# Lab1_Konovalov_USB_RS485.net
KiCad netlist of a schematic drawn in Altium Designer
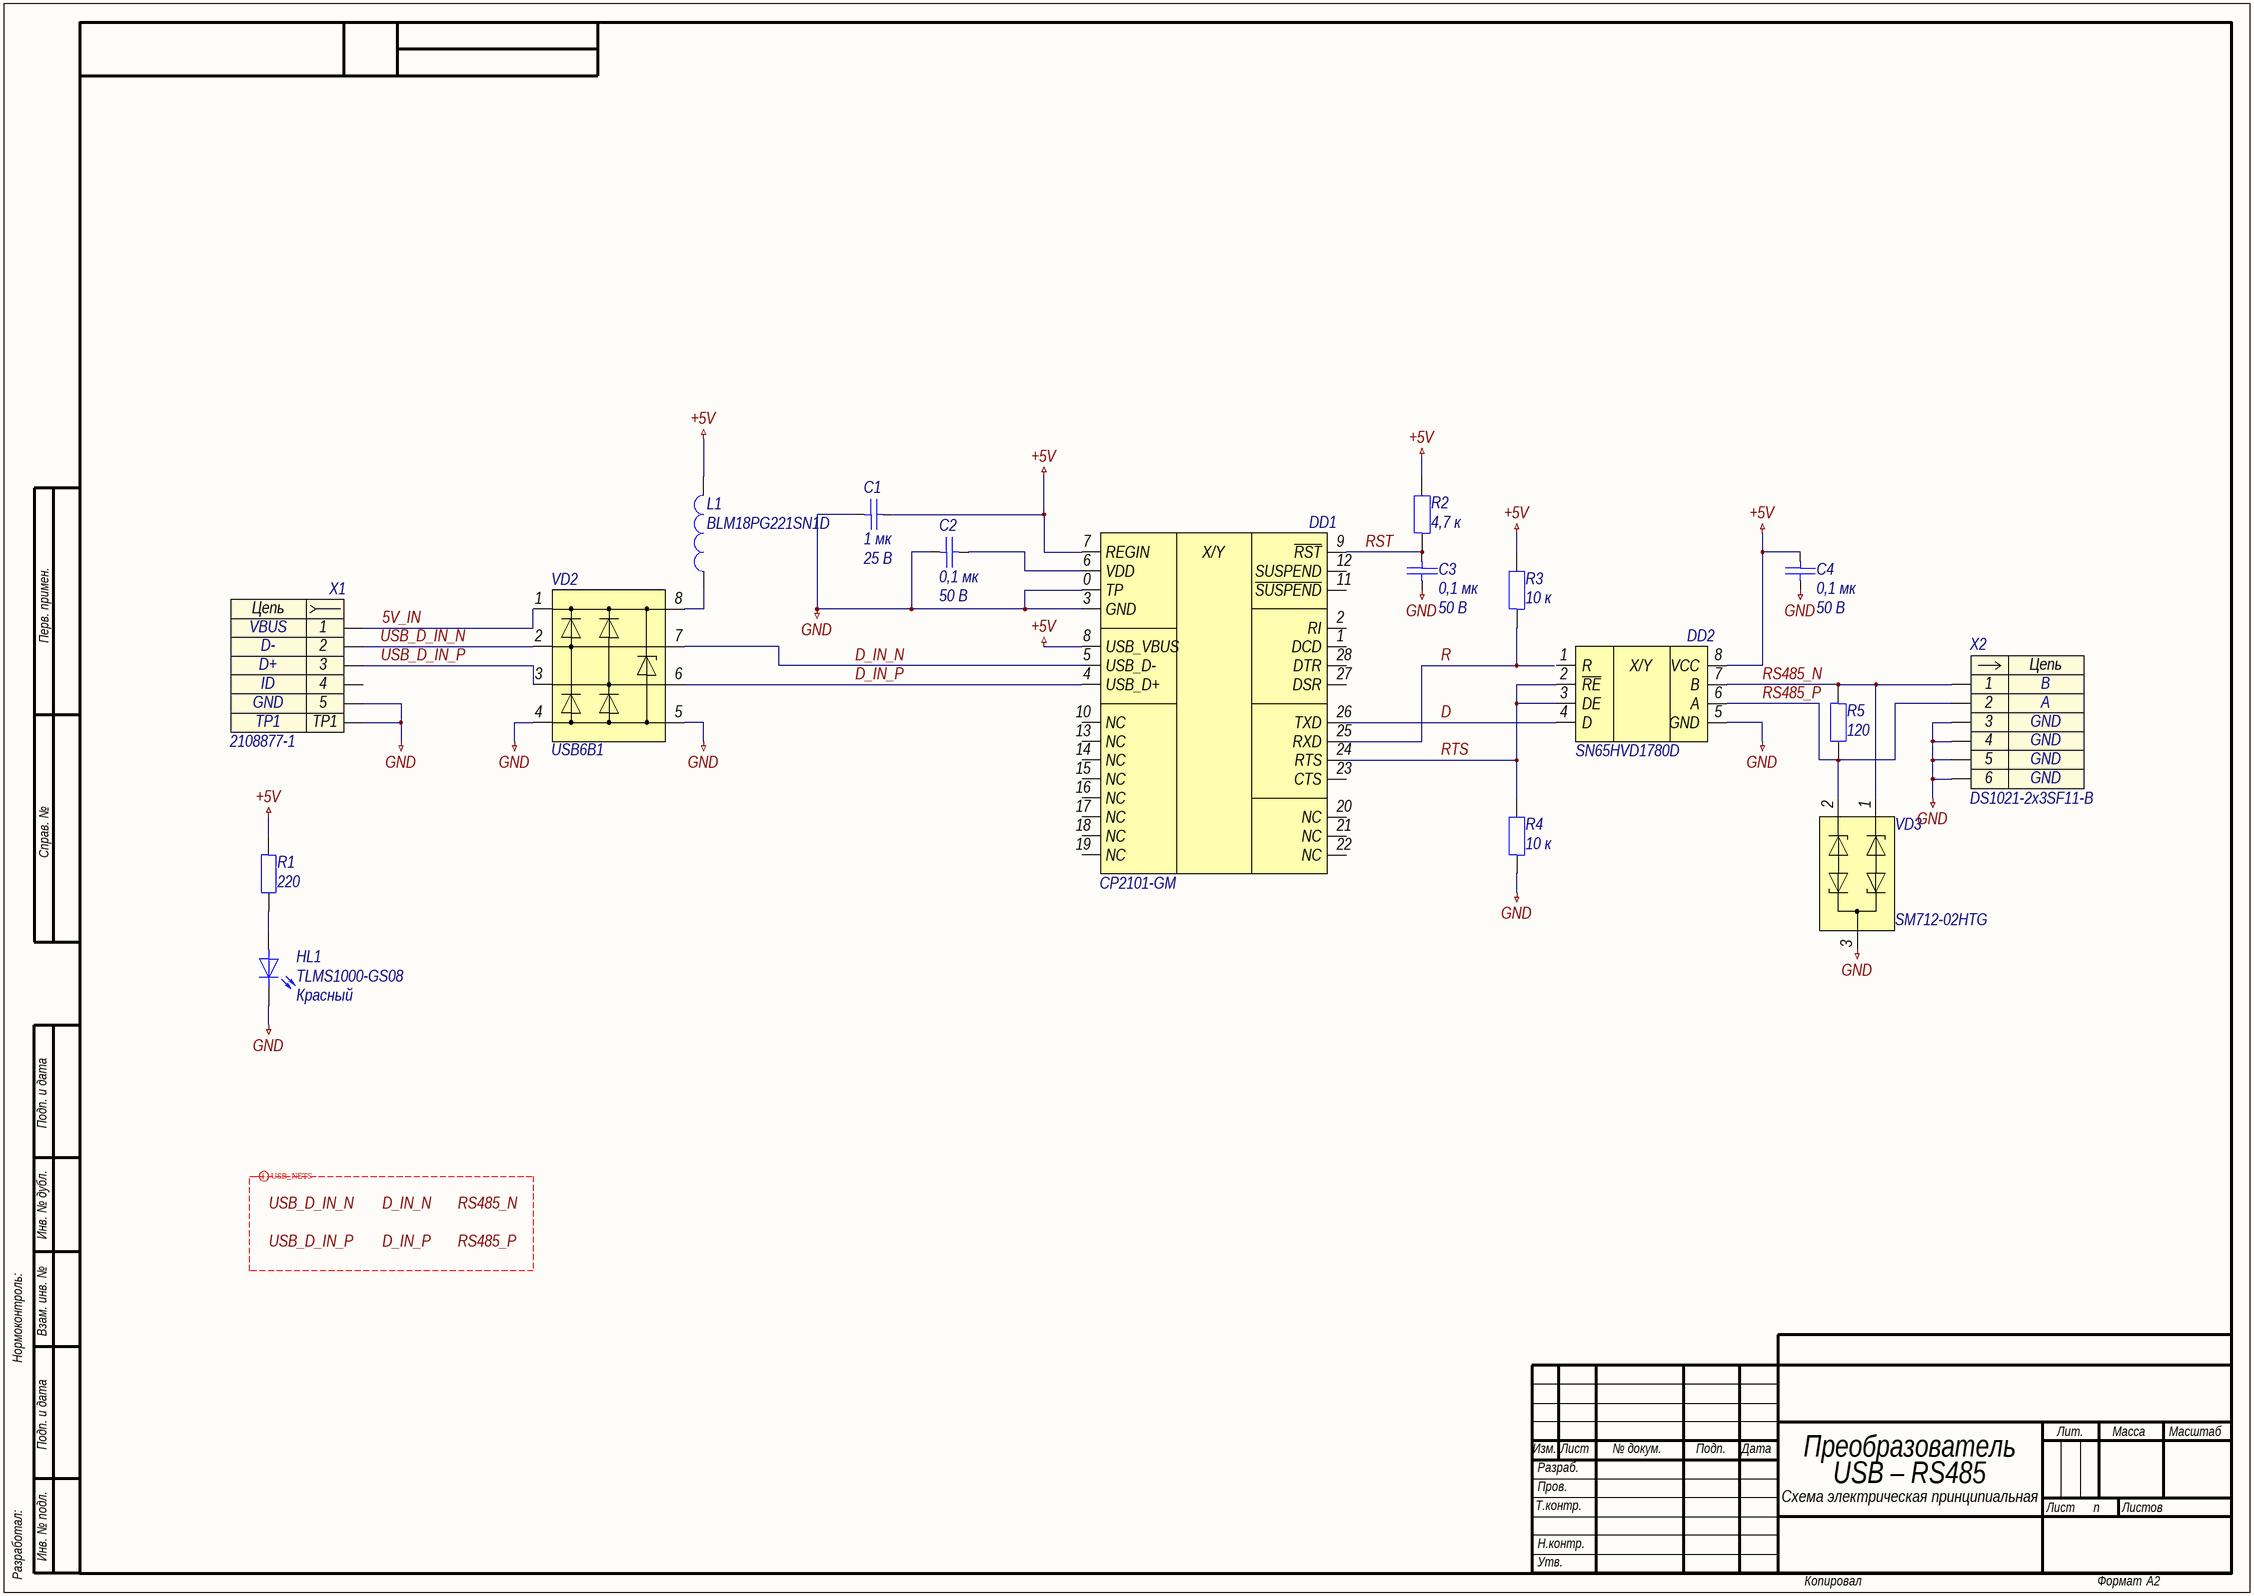
[diagram p0: Lab1_Konovalov_USB_RS485.SchDoc]

(export (version "E")
  (design (tool "Eeschema 10.0.6"))
  (components
    (comp (ref "C1")
      (value "1 мк")
      (footprint "C0603")
      (description "=Описание")
      (fields (field (name "НАПРЯЖЕНИЕ") "25 В"))
      (libsource (lib "Database_Students") (part "C-NONPOLAR"))
    )
    (comp (ref "C2")
      (value "0,1 мк")
      (footprint "C0603")
      (description "=Описание")
      (fields (field (name "НАПРЯЖЕНИЕ") "50 В"))
      (libsource (lib "Database_Students") (part "C-NONPOLAR"))
    )
    (comp (ref "C3")
      (value "0,1 мк")
      (footprint "C0603")
      (description "=Описание")
      (fields (field (name "НАПРЯЖЕНИЕ") "50 В"))
      (libsource (lib "Database_Students") (part "C-NONPOLAR"))
    )
    (comp (ref "C4")
      (value "0,1 мк")
      (footprint "C0603")
      (description "=Описание")
      (fields (field (name "НАПРЯЖЕНИЕ") "50 В"))
      (libsource (lib "Database_Students") (part "C-NONPOLAR"))
    )
    (comp (ref "DD1")
      (value "CP2101-GM")
      (footprint "QFN-28-500X500X90")
      (description "=Описание")
      (libsource (lib "Database_Students") (part "CP2101-GM"))
    )
    (comp (ref "DD2")
      (value "SN65HVD1780D")
      (footprint "SOIC-8")
      (description "=Описание")
      (libsource (lib "Database_Students") (part "SN65HVD1780D"))
    )
    (comp (ref "HL1")
      (value "TLMS1000-GS08")
      (footprint "HL0603")
      (description "=Описание")
      (fields (field (name "COLOUR") "Красный"))
      (libsource (lib "Database_Students") (part "LED-COMMON"))
    )
    (comp (ref "L1")
      (value "BLM18PG221SN1D")
      (footprint "BLM-2-0603")
      (description "=Описание")
      (libsource (lib "Database_Students") (part "FERRITE-BEAD"))
    )
    (comp (ref "R1")
      (value "220")
      (footprint "R0603")
      (description "=Описание")
      (libsource (lib "Database_Students") (part "R-COMMON"))
    )
    (comp (ref "R2")
      (value "4,7 к")
      (footprint "R0603")
      (description "=Описание")
      (libsource (lib "Database_Students") (part "R-COMMON"))
    )
    (comp (ref "R3")
      (value "10 к")
      (footprint "R0603")
      (description "=Описание")
      (libsource (lib "Database_Students") (part "R-COMMON"))
    )
    (comp (ref "R4")
      (value "10 к")
      (footprint "R0603")
      (description "=Описание")
      (libsource (lib "Database_Students") (part "R-COMMON"))
    )
    (comp (ref "R5")
      (value "120")
      (footprint "R0603")
      (description "=Описание")
      (libsource (lib "Database_Students") (part "R-COMMON"))
    )
    (comp (ref "VD2")
      (value "USB6B1")
      (footprint "SO-8")
      (description "=Описание")
      (libsource (lib "Database_Students") (part "USB6B1"))
    )
    (comp (ref "VD3")
      (value "SM712-02HTG")
      (footprint "SOT23-3")
      (description "=Описание")
      (libsource (lib "Database_Students") (part "SM712-02HTG"))
    )
    (comp (ref "X1")
      (value "2108877-1")
      (footprint "2108877-1")
      (description "=Описание")
      (libsource (lib "Database_Students") (part "HEADER-5-TP1-SCT"))
    )
    (comp (ref "X2")
      (value "DS1021-2x3SF11-B")
      (footprint "DS1021-2X3SF11-B")
      (description "=Описание")
      (libsource (lib "Database_Students") (part "HEADER-6-PLG"))
    )
  )
  (nets
    (net (code "1") (name "+5V") (class "Default")
      (node (ref "C1") (pin "1") (pinfunction "1_1") (pintype "passive"))
      (node (ref "C4") (pin "2") (pinfunction "2_2") (pintype "passive"))
      (node (ref "DD1") (pin "7") (pinfunction "REGIN_7") (pintype "passive"))
      (node (ref "DD1") (pin "8") (pinfunction "USB_VBUS_8") (pintype "passive"))
      (node (ref "DD2") (pin "8") (pinfunction "VCC_8") (pintype "passive"))
      (node (ref "L1") (pin "2") (pinfunction "2_2") (pintype "passive"))
      (node (ref "R1") (pin "1") (pinfunction "1_1") (pintype "passive"))
      (node (ref "R2") (pin "2") (pinfunction "2_2") (pintype "passive"))
      (node (ref "R3") (pin "2") (pinfunction "2_2") (pintype "passive"))
    )
    (net (code "2") (name "/5V_IN") (class "Default")
      (node (ref "VD2") (pin "1") (pinfunction "1_1") (pintype "passive"))
      (node (ref "X1") (pin "1") (pinfunction "1_1") (pintype "passive"))
    )
    (net (code "3") (name "/D") (class "Default")
      (node (ref "DD1") (pin "26") (pinfunction "TXD_26") (pintype "passive"))
      (node (ref "DD2") (pin "4") (pinfunction "D_4") (pintype "passive"))
    )
    (net (code "4") (name "/D_IN_N") (class "Default")
      (node (ref "DD1") (pin "5") (pinfunction "USB_D-_5") (pintype "passive"))
      (node (ref "VD2") (pin "7") (pinfunction "7_7") (pintype "passive"))
    )
    (net (code "5") (name "/D_IN_P") (class "Default")
      (node (ref "DD1") (pin "4") (pinfunction "USB_D+_4") (pintype "passive"))
      (node (ref "VD2") (pin "6") (pinfunction "6_6") (pintype "passive"))
    )
    (net (code "6") (name "/R") (class "Default")
      (node (ref "DD1") (pin "25") (pinfunction "RXD_25") (pintype "passive"))
      (node (ref "R3") (pin "1") (pinfunction "1_1") (pintype "passive"))
    )
    (net (code "7") (name "/RS485_N") (class "Default")
      (node (ref "DD2") (pin "7") (pinfunction "B_7") (pintype "passive"))
      (node (ref "R5") (pin "1") (pinfunction "1_1") (pintype "passive"))
      (node (ref "VD3") (pin "1") (pinfunction "1_1") (pintype "passive"))
      (node (ref "X2") (pin "1") (pinfunction "1_1") (pintype "passive"))
    )
    (net (code "8") (name "/RS485_P") (class "Default")
      (node (ref "DD2") (pin "6") (pinfunction "A_6") (pintype "passive"))
      (node (ref "R5") (pin "2") (pinfunction "2_2") (pintype "passive"))
      (node (ref "VD3") (pin "2") (pinfunction "2_2") (pintype "passive"))
      (node (ref "X2") (pin "2") (pinfunction "2_2") (pintype "passive"))
    )
    (net (code "9") (name "/RST") (class "Default")
      (node (ref "C3") (pin "2") (pinfunction "2_2") (pintype "passive"))
      (node (ref "DD1") (pin "9") (pinfunction "~{RST}_9") (pintype "passive"))
      (node (ref "R2") (pin "1") (pinfunction "1_1") (pintype "passive"))
    )
    (net (code "10") (name "/RTS") (class "Default")
      (node (ref "DD1") (pin "24") (pinfunction "RTS_24") (pintype "passive"))
      (node (ref "DD2") (pin "2") (pinfunction "~{RE}_2") (pintype "passive"))
      (node (ref "DD2") (pin "3") (pinfunction "DE_3") (pintype "passive"))
      (node (ref "R4") (pin "2") (pinfunction "2_2") (pintype "passive"))
    )
    (net (code "11") (name "/USB_D_IN_N") (class "Default")
      (node (ref "VD2") (pin "2") (pinfunction "2_2") (pintype "passive"))
      (node (ref "X1") (pin "2") (pinfunction "2_2") (pintype "passive"))
    )
    (net (code "12") (name "/USB_D_IN_P") (class "Default")
      (node (ref "VD2") (pin "3") (pinfunction "3_3") (pintype "passive"))
      (node (ref "X1") (pin "3") (pinfunction "3_3") (pintype "passive"))
    )
    (net (code "13") (name "GND") (class "Default")
      (node (ref "C1") (pin "2") (pinfunction "2_2") (pintype "passive"))
      (node (ref "C2") (pin "2") (pinfunction "2_2") (pintype "passive"))
      (node (ref "C3") (pin "1") (pinfunction "1_1") (pintype "passive"))
      (node (ref "C4") (pin "1") (pinfunction "1_1") (pintype "passive"))
      (node (ref "DD1") (pin "0") (pinfunction "TP_0") (pintype "passive"))
      (node (ref "DD1") (pin "3") (pinfunction "GND_3") (pintype "passive"))
      (node (ref "DD2") (pin "5") (pinfunction "GND_5") (pintype "passive"))
      (node (ref "HL1") (pin "1") (pinfunction "1_1") (pintype "passive"))
      (node (ref "R4") (pin "1") (pinfunction "1_1") (pintype "passive"))
      (node (ref "VD2") (pin "4") (pinfunction "4_4") (pintype "passive"))
      (node (ref "VD2") (pin "5") (pinfunction "5_5") (pintype "passive"))
      (node (ref "VD3") (pin "3") (pinfunction "3_3") (pintype "passive"))
      (node (ref "X1") (pin "5") (pinfunction "5_5") (pintype "passive"))
      (node (ref "X1") (pin "TP1") (pinfunction "TP1_TP1") (pintype "passive"))
      (node (ref "X2") (pin "3") (pinfunction "3_3") (pintype "passive"))
      (node (ref "X2") (pin "4") (pinfunction "4_4") (pintype "passive"))
      (node (ref "X2") (pin "5") (pinfunction "5_5") (pintype "passive"))
      (node (ref "X2") (pin "6") (pinfunction "6_6") (pintype "passive"))
    )
    (net (code "14") (name "Net-(DD1-VDD)") (class "Default")
      (node (ref "C2") (pin "1") (pinfunction "1_1") (pintype "passive"))
      (node (ref "DD1") (pin "6") (pinfunction "VDD_6") (pintype "passive"))
    )
    (net (code "15") (name "Net-(HL1-Pad2)") (class "Default")
      (node (ref "HL1") (pin "2") (pinfunction "2_2") (pintype "passive"))
      (node (ref "R1") (pin "2") (pinfunction "2_2") (pintype "passive"))
    )
    (net (code "16") (name "Net-(L1-Pad1)") (class "Default")
      (node (ref "L1") (pin "1") (pinfunction "1_1") (pintype "passive"))
      (node (ref "VD2") (pin "8") (pinfunction "8_8") (pintype "passive"))
    )
    (net (code "17") (name "unconnected-(DD1-CTS-Pad23)") (class "Default")
      (node (ref "DD1") (pin "23") (pinfunction "CTS_23") (pintype "passive"))
    )
    (net (code "18") (name "unconnected-(DD1-DCD-Pad1)") (class "Default")
      (node (ref "DD1") (pin "1") (pinfunction "DCD_1") (pintype "passive"))
    )
    (net (code "19") (name "unconnected-(DD1-DSR-Pad27)") (class "Default")
      (node (ref "DD1") (pin "27") (pinfunction "DSR_27") (pintype "passive"))
    )
    (net (code "20") (name "unconnected-(DD1-DTR-Pad28)") (class "Default")
      (node (ref "DD1") (pin "28") (pinfunction "DTR_28") (pintype "passive"))
    )
    (net (code "21") (name "unconnected-(DD1-NC-Pad10)") (class "Default")
      (node (ref "DD1") (pin "10") (pinfunction "NC_10") (pintype "passive"))
    )
    (net (code "22") (name "unconnected-(DD1-NC-Pad13)") (class "Default")
      (node (ref "DD1") (pin "13") (pinfunction "NC_13") (pintype "passive"))
    )
    (net (code "23") (name "unconnected-(DD1-NC-Pad14)") (class "Default")
      (node (ref "DD1") (pin "14") (pinfunction "NC_14") (pintype "passive"))
    )
    (net (code "24") (name "unconnected-(DD1-NC-Pad15)") (class "Default")
      (node (ref "DD1") (pin "15") (pinfunction "NC_15") (pintype "passive"))
    )
    (net (code "25") (name "unconnected-(DD1-NC-Pad16)") (class "Default")
      (node (ref "DD1") (pin "16") (pinfunction "NC_16") (pintype "passive"))
    )
    (net (code "26") (name "unconnected-(DD1-NC-Pad17)") (class "Default")
      (node (ref "DD1") (pin "17") (pinfunction "NC_17") (pintype "passive"))
    )
    (net (code "27") (name "unconnected-(DD1-NC-Pad18)") (class "Default")
      (node (ref "DD1") (pin "18") (pinfunction "NC_18") (pintype "passive"))
    )
    (net (code "28") (name "unconnected-(DD1-NC-Pad19)") (class "Default")
      (node (ref "DD1") (pin "19") (pinfunction "NC_19") (pintype "passive"))
    )
    (net (code "29") (name "unconnected-(DD1-NC-Pad20)") (class "Default")
      (node (ref "DD1") (pin "20") (pinfunction "NC_20") (pintype "passive"))
    )
    (net (code "30") (name "unconnected-(DD1-NC-Pad21)") (class "Default")
      (node (ref "DD1") (pin "21") (pinfunction "NC_21") (pintype "passive"))
    )
    (net (code "31") (name "unconnected-(DD1-NC-Pad22)") (class "Default")
      (node (ref "DD1") (pin "22") (pinfunction "NC_22") (pintype "passive"))
    )
    (net (code "32") (name "unconnected-(DD1-RI-Pad2)") (class "Default")
      (node (ref "DD1") (pin "2") (pinfunction "RI_2") (pintype "passive"))
    )
    (net (code "33") (name "unconnected-(DD1-SUSPEND-Pad12)") (class "Default")
      (node (ref "DD1") (pin "12") (pinfunction "SUSPEND_12") (pintype "passive"))
    )
    (net (code "34") (name "unconnected-(DD1-~{SUSPEND}-Pad11)") (class "Default")
      (node (ref "DD1") (pin "11") (pinfunction "~{SUSPEND}_11") (pintype "passive"))
    )
    (net (code "35") (name "unconnected-(DD2-R-Pad1)") (class "Default")
      (node (ref "DD2") (pin "1") (pinfunction "R_1") (pintype "passive"))
    )
    (net (code "36") (name "unconnected-(X1-Pad4)") (class "Default")
      (node (ref "X1") (pin "4") (pinfunction "4_4") (pintype "passive"))
    )
  )
)
